# arduino_Uno_Rev3e.net
KiCad netlist of a schematic drawn in EAGLE
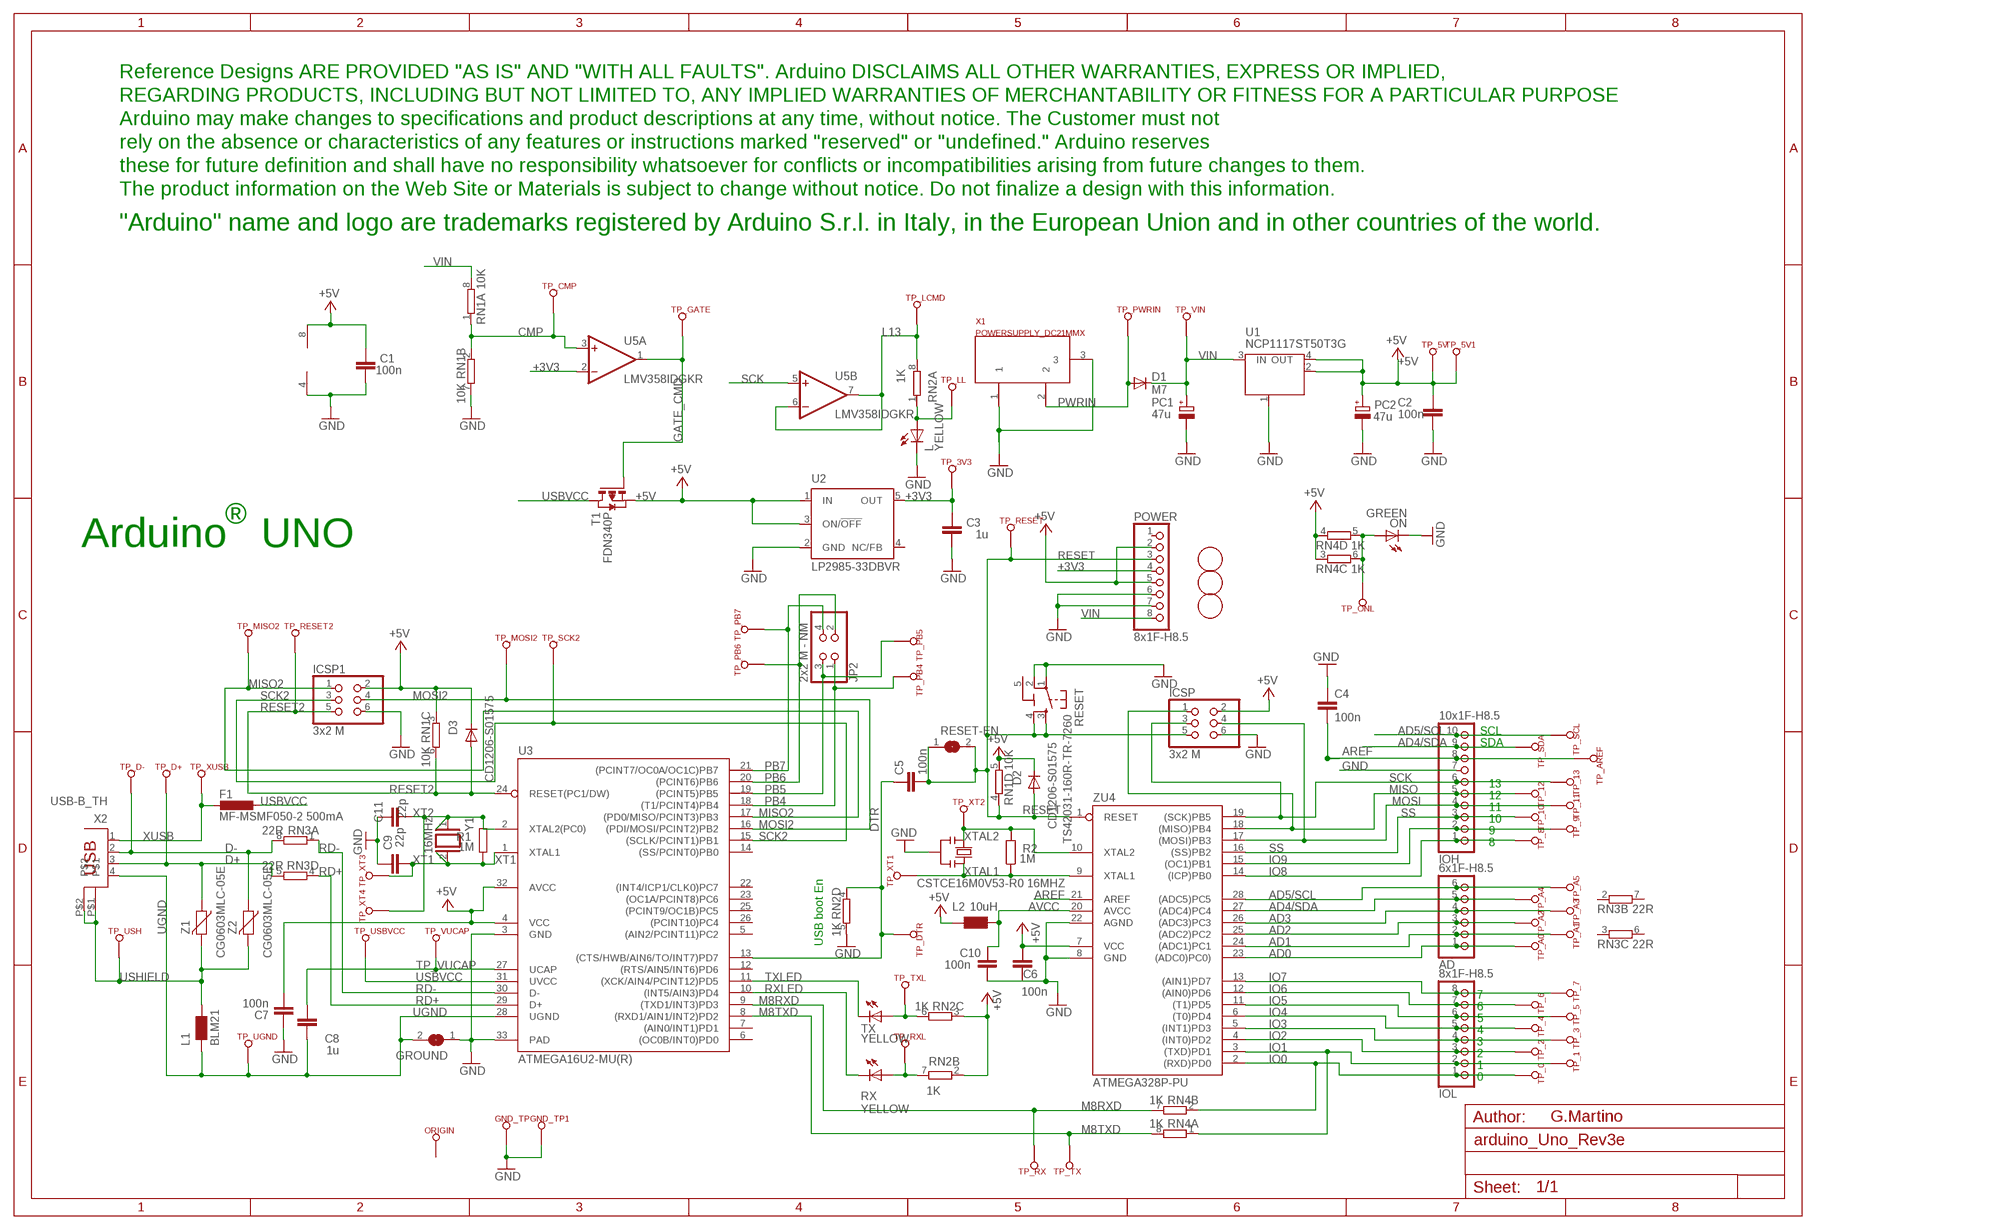
[diagram p0: schematic, sheet 1]

(export (version "E")
  (design (tool "Eeschema 10.0.6"))
  (components
    (comp (ref "AD")
      (value "6x1F-H8.5")
      (footprint "eagle-import:1X06")
      (libsource (lib "eagle-import") (part "PINHD-1X6"))
    )
    (comp (ref "C1")
      (value "100n")
      (footprint "eagle-import:C0603-ROUND")
      (libsource (lib "eagle-import") (part "C-EU0603-RND"))
    )
    (comp (ref "C2")
      (value "100n")
      (footprint "eagle-import:C0603-ROUND")
      (libsource (lib "eagle-import") (part "C-EU0603-RND"))
    )
    (comp (ref "C3")
      (value "1u")
      (footprint "eagle-import:C0603-ROUND")
      (libsource (lib "eagle-import") (part "C-EU0603-RND"))
    )
    (comp (ref "C4")
      (value "100n")
      (footprint "eagle-import:C0603-ROUND")
      (libsource (lib "eagle-import") (part "C-EU0603-RND"))
    )
    (comp (ref "C5")
      (value "100n")
      (footprint "eagle-import:C0603-ROUND")
      (libsource (lib "eagle-import") (part "C-EU0603-RND"))
    )
    (comp (ref "C6")
      (value "100n")
      (footprint "eagle-import:C0603-ROUND")
      (libsource (lib "eagle-import") (part "C-EU0603-RND"))
    )
    (comp (ref "C7")
      (value "100n")
      (footprint "eagle-import:C0603-ROUND")
      (libsource (lib "eagle-import") (part "C-EU0603-RND"))
    )
    (comp (ref "C8")
      (value "1u")
      (footprint "eagle-import:C0603-ROUND")
      (libsource (lib "eagle-import") (part "C-EU0603-RND"))
    )
    (comp (ref "C9")
      (value "22p")
      (footprint "eagle-import:C0603-ROUND")
      (libsource (lib "eagle-import") (part "C-EU0603-RND"))
    )
    (comp (ref "C10")
      (value "100n")
      (footprint "eagle-import:C0603-ROUND")
      (libsource (lib "eagle-import") (part "C-EU0603-RND"))
    )
    (comp (ref "C11")
      (value "22p")
      (footprint "eagle-import:C0603-ROUND")
      (libsource (lib "eagle-import") (part "C-EU0603-RND"))
    )
    (comp (ref "D1")
      (value "M7")
      (footprint "eagle-import:SMB")
      (libsource (lib "eagle-import") (part "DIODE-SMB"))
    )
    (comp (ref "D2")
      (value "CD1206-S01575")
      (footprint "eagle-import:MINIMELF")
      (libsource (lib "eagle-import") (part "DIODE-MINIMELF"))
    )
    (comp (ref "D3")
      (value "CD1206-S01575")
      (footprint "eagle-import:MINIMELF")
      (libsource (lib "eagle-import") (part "DIODE-MINIMELF"))
    )
    (comp (ref "F1")
      (value "MF-MSMF050-2 500mA")
      (footprint "eagle-import:L1812")
      (libsource (lib "eagle-import") (part "L-EUL1812"))
    )
    (comp (ref "FD1")
      (value "FIDUCIALMOUNT")
      (footprint "eagle-import:FIDUCIA-MOUNT")
      (libsource (lib "eagle-import") (part "FIDUCIALMOUNT"))
    )
    (comp (ref "FD2")
      (value "FIDUCIALMOUNT")
      (footprint "eagle-import:FIDUCIA-MOUNT")
      (libsource (lib "eagle-import") (part "FIDUCIALMOUNT"))
    )
    (comp (ref "FD3")
      (value "FIDUCIALMOUNT")
      (footprint "eagle-import:FIDUCIA-MOUNT")
      (libsource (lib "eagle-import") (part "FIDUCIALMOUNT"))
    )
    (comp (ref "GND_TP")
      (value "TP_SP")
      (footprint "eagle-import:TP-SP")
      (libsource (lib "eagle-import") (part "TP_SP"))
    )
    (comp (ref "GND_TP1")
      (value "TP_SP")
      (footprint "eagle-import:TP-SP")
      (libsource (lib "eagle-import") (part "TP_SP"))
    )
    (comp (ref "GROUND")
      (value "SJ")
      (footprint "eagle-import:SJ")
      (libsource (lib "eagle-import") (part "SJ"))
    )
    (comp (ref "ICSP")
      (value "3x2 M")
      (footprint "eagle-import:2X03")
      (libsource (lib "eagle-import") (part "PINHD-2X3"))
    )
    (comp (ref "ICSP1")
      (value "3x2 M")
      (footprint "eagle-import:2X03")
      (libsource (lib "eagle-import") (part "PINHD-2X3"))
    )
    (comp (ref "IOH")
      (value "10x1F-H8.5")
      (footprint "eagle-import:1X10")
      (libsource (lib "eagle-import") (part "PINHD-1X10_ARD"))
    )
    (comp (ref "IOL")
      (value "8x1F-H8.5")
      (footprint "eagle-import:1X08")
      (libsource (lib "eagle-import") (part "PINHD-1X8"))
    )
    (comp (ref "JP2")
      (value "2x2 M - NM")
      (footprint "eagle-import:2X02")
      (libsource (lib "eagle-import") (part "PINHD-2X2"))
    )
    (comp (ref "L")
      (value "YELLOW")
      (footprint "eagle-import:CHIP-LED0805")
      (libsource (lib "eagle-import") (part "LEDCHIP-LED0805"))
    )
    (comp (ref "L1")
      (value "BLM21")
      (footprint "eagle-import:0805")
      (libsource (lib "eagle-import") (part "WE-CBF_0805"))
    )
    (comp (ref "L2")
      (value "10uH")
      (footprint "eagle-import:0805")
      (fields (field (name "PART_NUMBER") "CV201210-100K"))
      (libsource (lib "eagle-import") (part "0715_CV201210-100K"))
    )
    (comp (ref "ON")
      (value "GREEN")
      (footprint "eagle-import:CHIP-LED0805")
      (libsource (lib "eagle-import") (part "LEDCHIP-LED0805"))
    )
    (comp (ref "ORIGIN")
      (value "TP_SP")
      (footprint "eagle-import:TP-SP")
      (libsource (lib "eagle-import") (part "TP_SP"))
    )
    (comp (ref "PC1")
      (value "47u")
      (footprint "eagle-import:PANASONIC_D")
      (libsource (lib "eagle-import") (part "CPOL-EUD"))
    )
    (comp (ref "PC2")
      (value "47u")
      (footprint "eagle-import:PANASONIC_D")
      (libsource (lib "eagle-import") (part "CPOL-EUD"))
    )
    (comp (ref "POWER")
      (value "8x1F-H8.5")
      (footprint "eagle-import:1X08")
      (libsource (lib "eagle-import") (part "PINHD-1X8"))
    )
    (comp (ref "R1")
      (value "1M")
      (footprint "eagle-import:R0603-ROUND")
      (libsource (lib "eagle-import") (part "R-EU_R0603"))
    )
    (comp (ref "R2")
      (value "1M")
      (footprint "eagle-import:R0603-ROUND")
      (libsource (lib "eagle-import") (part "R-EU_R0603"))
    )
    (comp (ref "RESET")
      (value "TS42031-160R-TR-7260")
      (footprint "eagle-import:TS42")
      (libsource (lib "eagle-import") (part "TS42"))
    )
    (comp (ref "RESET-EN")
      (value "SJ")
      (footprint "eagle-import:SJ")
      (libsource (lib "eagle-import") (part "SJ"))
    )
    (comp (ref "RN1")
      (value "10K")
      (footprint "eagle-import:CAY16")
      (libsource (lib "eagle-import") (part "4R-NCAY16"))
    )
    (comp (ref "RN2")
      (value "1K")
      (footprint "eagle-import:CAY16")
      (libsource (lib "eagle-import") (part "4R-NCAY16"))
    )
    (comp (ref "RN3")
      (value "22R")
      (footprint "eagle-import:CAY16")
      (libsource (lib "eagle-import") (part "4R-NCAY16"))
    )
    (comp (ref "RN4")
      (value "1K")
      (footprint "eagle-import:CAY16")
      (libsource (lib "eagle-import") (part "4R-NCAY16"))
    )
    (comp (ref "RX")
      (value "YELLOW")
      (footprint "eagle-import:CHIP-LED0805")
      (libsource (lib "eagle-import") (part "LEDCHIP-LED0805"))
    )
    (comp (ref "T1")
      (value "FDN340P")
      (footprint "eagle-import:SOT-23")
      (libsource (lib "eagle-import") (part "PMOSSOT23"))
    )
    (comp (ref "TP_0")
      (value "TP_SP")
      (footprint "eagle-import:TP-SP")
      (libsource (lib "eagle-import") (part "TP_SP"))
    )
    (comp (ref "TP_1")
      (value "TP_SP")
      (footprint "eagle-import:TP-SP")
      (libsource (lib "eagle-import") (part "TP_SP"))
    )
    (comp (ref "TP_2")
      (value "TP_SP")
      (footprint "eagle-import:TP-SP")
      (libsource (lib "eagle-import") (part "TP_SP"))
    )
    (comp (ref "TP_3")
      (value "TP_SP")
      (footprint "eagle-import:TP-SP")
      (libsource (lib "eagle-import") (part "TP_SP"))
    )
    (comp (ref "TP_3V3")
      (value "TP_SP")
      (footprint "eagle-import:TP-SP")
      (libsource (lib "eagle-import") (part "TP_SP"))
    )
    (comp (ref "TP_4")
      (value "TP_SP")
      (footprint "eagle-import:TP-SP")
      (libsource (lib "eagle-import") (part "TP_SP"))
    )
    (comp (ref "TP_5")
      (value "TP_SP")
      (footprint "eagle-import:TP-SP")
      (libsource (lib "eagle-import") (part "TP_SP"))
    )
    (comp (ref "TP_5V")
      (value "TP_SP")
      (footprint "eagle-import:TP-SP")
      (libsource (lib "eagle-import") (part "TP_SP"))
    )
    (comp (ref "TP_5V1")
      (value "TP_SP")
      (footprint "eagle-import:TP-SP")
      (libsource (lib "eagle-import") (part "TP_SP"))
    )
    (comp (ref "TP_6")
      (value "TP_SP")
      (footprint "eagle-import:TP-SP")
      (libsource (lib "eagle-import") (part "TP_SP"))
    )
    (comp (ref "TP_7")
      (value "TP_SP")
      (footprint "eagle-import:TP-SP")
      (libsource (lib "eagle-import") (part "TP_SP"))
    )
    (comp (ref "TP_8")
      (value "TP_SP")
      (footprint "eagle-import:TP-SP")
      (libsource (lib "eagle-import") (part "TP_SP"))
    )
    (comp (ref "TP_9")
      (value "TP_SP")
      (footprint "eagle-import:TP-SP")
      (libsource (lib "eagle-import") (part "TP_SP"))
    )
    (comp (ref "TP_10")
      (value "TP_SP")
      (footprint "eagle-import:TP-SP")
      (libsource (lib "eagle-import") (part "TP_SP"))
    )
    (comp (ref "TP_11")
      (value "TP_SP")
      (footprint "eagle-import:TP-SP")
      (libsource (lib "eagle-import") (part "TP_SP"))
    )
    (comp (ref "TP_12")
      (value "TP_SP")
      (footprint "eagle-import:TP-SP")
      (libsource (lib "eagle-import") (part "TP_SP"))
    )
    (comp (ref "TP_13")
      (value "TP_SP")
      (footprint "eagle-import:TP-SP")
      (libsource (lib "eagle-import") (part "TP_SP"))
    )
    (comp (ref "TP_A0")
      (value "TP_SP")
      (footprint "eagle-import:TP-SP")
      (libsource (lib "eagle-import") (part "TP_SP"))
    )
    (comp (ref "TP_A1")
      (value "TP_SP")
      (footprint "eagle-import:TP-SP")
      (libsource (lib "eagle-import") (part "TP_SP"))
    )
    (comp (ref "TP_A2")
      (value "TP_SP")
      (footprint "eagle-import:TP-SP")
      (libsource (lib "eagle-import") (part "TP_SP"))
    )
    (comp (ref "TP_A3")
      (value "TP_SP")
      (footprint "eagle-import:TP-SP")
      (libsource (lib "eagle-import") (part "TP_SP"))
    )
    (comp (ref "TP_A4")
      (value "TP_SP")
      (footprint "eagle-import:TP-SP")
      (libsource (lib "eagle-import") (part "TP_SP"))
    )
    (comp (ref "TP_A5")
      (value "TP_SP")
      (footprint "eagle-import:TP-SP")
      (libsource (lib "eagle-import") (part "TP_SP"))
    )
    (comp (ref "TP_AREF")
      (value "TP_SP")
      (footprint "eagle-import:TP-SP")
      (libsource (lib "eagle-import") (part "TP_SP"))
    )
    (comp (ref "TP_CMP")
      (value "TP_SP")
      (footprint "eagle-import:TP-SP")
      (libsource (lib "eagle-import") (part "TP_SP"))
    )
    (comp (ref "TP_D+")
      (value "TP_SP")
      (footprint "eagle-import:TP-SP")
      (libsource (lib "eagle-import") (part "TP_SP"))
    )
    (comp (ref "TP_D-")
      (value "TP_SP")
      (footprint "eagle-import:TP-SP")
      (libsource (lib "eagle-import") (part "TP_SP"))
    )
    (comp (ref "TP_DTR")
      (value "TP_SP")
      (footprint "eagle-import:TP-SP")
      (libsource (lib "eagle-import") (part "TP_SP"))
    )
    (comp (ref "TP_GATE")
      (value "TP_SP")
      (footprint "eagle-import:TP-SP")
      (libsource (lib "eagle-import") (part "TP_SP"))
    )
    (comp (ref "TP_LCMD")
      (value "TP_SP")
      (footprint "eagle-import:TP-SP")
      (libsource (lib "eagle-import") (part "TP_SP"))
    )
    (comp (ref "TP_LL")
      (value "TP_SP")
      (footprint "eagle-import:TP-SP")
      (libsource (lib "eagle-import") (part "TP_SP"))
    )
    (comp (ref "TP_MISO2")
      (value "TP_SP")
      (footprint "eagle-import:TP-SP")
      (libsource (lib "eagle-import") (part "TP_SP"))
    )
    (comp (ref "TP_MOSI2")
      (value "TP_SP")
      (footprint "eagle-import:TP-SP")
      (libsource (lib "eagle-import") (part "TP_SP"))
    )
    (comp (ref "TP_ONL")
      (value "TP_SP")
      (footprint "eagle-import:TP-SP")
      (libsource (lib "eagle-import") (part "TP_SP"))
    )
    (comp (ref "TP_PB4")
      (value "TP_SP")
      (footprint "eagle-import:TP-SP")
      (libsource (lib "eagle-import") (part "TP_SP"))
    )
    (comp (ref "TP_PB5")
      (value "TP_SP")
      (footprint "eagle-import:TP-SP")
      (libsource (lib "eagle-import") (part "TP_SP"))
    )
    (comp (ref "TP_PB6")
      (value "TP_SP")
      (footprint "eagle-import:TP-SP")
      (libsource (lib "eagle-import") (part "TP_SP"))
    )
    (comp (ref "TP_PB7")
      (value "TP_SP")
      (footprint "eagle-import:TP-SP")
      (libsource (lib "eagle-import") (part "TP_SP"))
    )
    (comp (ref "TP_PWRIN")
      (value "TP_SP")
      (footprint "eagle-import:TP-SP")
      (libsource (lib "eagle-import") (part "TP_SP"))
    )
    (comp (ref "TP_RESET")
      (value "TP_SP")
      (footprint "eagle-import:TP-SP")
      (libsource (lib "eagle-import") (part "TP_SP"))
    )
    (comp (ref "TP_RESET2")
      (value "TP_SP")
      (footprint "eagle-import:TP-SP")
      (libsource (lib "eagle-import") (part "TP_SP"))
    )
    (comp (ref "TP_RX")
      (value "TP_SP")
      (footprint "eagle-import:TP-SP")
      (libsource (lib "eagle-import") (part "TP_SP"))
    )
    (comp (ref "TP_RXL")
      (value "TP_SP")
      (footprint "eagle-import:TP-SP")
      (libsource (lib "eagle-import") (part "TP_SP"))
    )
    (comp (ref "TP_SCK2")
      (value "TP_SP")
      (footprint "eagle-import:TP-SP")
      (libsource (lib "eagle-import") (part "TP_SP"))
    )
    (comp (ref "TP_SCL")
      (value "TP_SP")
      (footprint "eagle-import:TP-SP")
      (libsource (lib "eagle-import") (part "TP_SP"))
    )
    (comp (ref "TP_SDA")
      (value "TP_SP")
      (footprint "eagle-import:TP-SP")
      (libsource (lib "eagle-import") (part "TP_SP"))
    )
    (comp (ref "TP_TX")
      (value "TP_SP")
      (footprint "eagle-import:TP-SP")
      (libsource (lib "eagle-import") (part "TP_SP"))
    )
    (comp (ref "TP_TXL")
      (value "TP_SP")
      (footprint "eagle-import:TP-SP")
      (libsource (lib "eagle-import") (part "TP_SP"))
    )
    (comp (ref "TP_UGND")
      (value "TP_SP")
      (footprint "eagle-import:TP-SP")
      (libsource (lib "eagle-import") (part "TP_SP"))
    )
    (comp (ref "TP_USBVCC")
      (value "TP_SP")
      (footprint "eagle-import:TP-SP")
      (libsource (lib "eagle-import") (part "TP_SP"))
    )
    (comp (ref "TP_USH")
      (value "TP_SP")
      (footprint "eagle-import:TP-SP")
      (libsource (lib "eagle-import") (part "TP_SP"))
    )
    (comp (ref "TP_VIN")
      (value "TP_SP")
      (footprint "eagle-import:TP-SP")
      (libsource (lib "eagle-import") (part "TP_SP"))
    )
    (comp (ref "TP_VUCAP")
      (value "TP_SP")
      (footprint "eagle-import:TP-SP")
      (libsource (lib "eagle-import") (part "TP_SP"))
    )
    (comp (ref "TP_XT1")
      (value "TP_SP")
      (footprint "eagle-import:TP-SP")
      (libsource (lib "eagle-import") (part "TP_SP"))
    )
    (comp (ref "TP_XT2")
      (value "TP_SP")
      (footprint "eagle-import:TP-SP")
      (libsource (lib "eagle-import") (part "TP_SP"))
    )
    (comp (ref "TP_XT3")
      (value "TP_SP")
      (footprint "eagle-import:TP-SP")
      (libsource (lib "eagle-import") (part "TP_SP"))
    )
    (comp (ref "TP_XT4")
      (value "TP_SP")
      (footprint "eagle-import:TP-SP")
      (libsource (lib "eagle-import") (part "TP_SP"))
    )
    (comp (ref "TP_XUSB")
      (value "TP_SP")
      (footprint "eagle-import:TP-SP")
      (libsource (lib "eagle-import") (part "TP_SP"))
    )
    (comp (ref "TX")
      (value "YELLOW")
      (footprint "eagle-import:CHIP-LED0805")
      (libsource (lib "eagle-import") (part "LEDCHIP-LED0805"))
    )
    (comp (ref "U$1")
      (value "DISCLAIMER")
      (footprint "eagle-import:DISCLAIMER")
      (libsource (lib "eagle-import") (part "DISCLAIMER"))
    )
    (comp (ref "U1")
      (value "NCP1117ST50T3G")
      (footprint "eagle-import:SOT223")
      (libsource (lib "eagle-import") (part "MC33269ST-3.3T3"))
    )
    (comp (ref "U2")
      (value "LP2985-33DBVR")
      (footprint "eagle-import:SOT23-DBV")
      (libsource (lib "eagle-import") (part "LP2985-XXDBVR33"))
    )
    (comp (ref "U3")
      (value "ATMEGA16U2-MU(R)")
      (footprint "eagle-import:MLF32")
      (libsource (lib "eagle-import") (part "ATMEGA16U2-MU"))
    )
    (comp (ref "U5")
      (value "LMV358IDGKR")
      (footprint "eagle-import:MSOP08")
      (libsource (lib "eagle-import") (part "LMV358?MMX"))
    )
    (comp (ref "X1")
      (value "POWERSUPPLY_DC21MMX")
      (footprint "eagle-import:POWERSUPPLY_DC-21MM")
      (libsource (lib "eagle-import") (part "POWERSUPPLY_DC21MMX"))
    )
    (comp (ref "X2")
      (value "USB-B_TH")
      (footprint "eagle-import:PN61729")
      (libsource (lib "eagle-import") (part "PN61729"))
    )
    (comp (ref "Y1")
      (value "16MHz")
      (footprint "eagle-import:QS")
      (libsource (lib "eagle-import") (part "XTAL/S"))
    )
    (comp (ref "Y2")
      (value "CSTCE16M0V53-R0 16MHZ")
      (footprint "eagle-import:RESONATOR")
      (libsource (lib "eagle-import") (part "RESONATORMU"))
    )
    (comp (ref "Z1")
      (value "CG0603MLC-05E")
      (footprint "eagle-import:CT_CN0603")
      (libsource (lib "eagle-import") (part "VARISTORCN0603"))
    )
    (comp (ref "Z2")
      (value "CG0603MLC-05E")
      (footprint "eagle-import:CT_CN0603")
      (libsource (lib "eagle-import") (part "VARISTORCN0603"))
    )
    (comp (ref "ZU4")
      (value "ATMEGA328P-PU")
      (footprint "eagle-import:DIL28-3")
      (libsource (lib "eagle-import") (part "ATMEGA328P-PU"))
    )
  )
  (nets
    (net (code "1") (name "+5V") (class "Default")
      (node (ref "C1") (pin "2") (pinfunction "2_2") (pintype "passive"))
      (node (ref "C2") (pin "2") (pinfunction "2_2") (pintype "passive"))
      (node (ref "C6") (pin "2") (pinfunction "2_2") (pintype "passive"))
      (node (ref "C7") (pin "1") (pinfunction "1_1") (pintype "passive"))
      (node (ref "D2") (pin "C") (pinfunction "C_C") (pintype "passive"))
      (node (ref "D3") (pin "C") (pinfunction "C_C") (pintype "passive"))
      (node (ref "ICSP") (pin "2") (pinfunction "2_2") (pintype "passive"))
      (node (ref "ICSP1") (pin "2") (pinfunction "2_2") (pintype "passive"))
      (node (ref "L2") (pin "1") (pinfunction "1_1") (pintype "passive"))
      (node (ref "PC2") (pin "+") (pinfunction "+_+") (pintype "passive"))
      (node (ref "POWER") (pin "2") (pinfunction "2_2") (pintype "passive"))
      (node (ref "POWER") (pin "5") (pinfunction "5_5") (pintype "passive"))
      (node (ref "RN1") (pin "3") (pinfunction "1_3") (pintype "passive"))
      (node (ref "RN1") (pin "5") (pinfunction "2_5") (pintype "passive"))
      (node (ref "RN2") (pin "2") (pinfunction "1_2") (pintype "passive"))
      (node (ref "RN2") (pin "3") (pinfunction "1_3") (pintype "passive"))
      (node (ref "RN4") (pin "3") (pinfunction "1_3") (pintype "passive"))
      (node (ref "RN4") (pin "4") (pinfunction "1_4") (pintype "passive"))
      (node (ref "T1") (pin "2") (pinfunction "S_2") (pintype "passive"))
      (node (ref "TP_5V") (pin "X") (pinfunction "TESTP_X") (pintype "passive"))
      (node (ref "TP_5V1") (pin "X") (pinfunction "TESTP_X") (pintype "passive"))
      (node (ref "U1") (pin "2") (pinfunction "OUT_2") (pintype "passive"))
      (node (ref "U1") (pin "4") (pinfunction "OUT_4") (pintype "passive"))
      (node (ref "U2") (pin "1") (pinfunction "IN_1") (pintype "input"))
      (node (ref "U2") (pin "3") (pinfunction "ON/~{OFF}_3") (pintype "input"))
      (node (ref "U3") (pin "32") (pinfunction "AVCC_32") (pintype "power_in"))
      (node (ref "U3") (pin "4") (pinfunction "VCC_4") (pintype "power_in"))
      (node (ref "U5") (pin "8") (pinfunction "V+_8") (pintype "power_in"))
      (node (ref "ZU4") (pin "7") (pinfunction "VCC_7") (pintype "power_in"))
    )
    (net (code "2") (name "/+3V3") (class "Default")
      (node (ref "C3") (pin "2") (pinfunction "2_2") (pintype "passive"))
      (node (ref "POWER") (pin "4") (pinfunction "4_4") (pintype "passive"))
      (node (ref "TP_3V3") (pin "X") (pinfunction "TESTP_X") (pintype "passive"))
      (node (ref "U2") (pin "5") (pinfunction "OUT_5") (pintype "passive"))
      (node (ref "U5") (pin "2") (pinfunction "-IN_2") (pintype "input"))
    )
    (net (code "3") (name "/5-GND") (class "Default")
      (node (ref "RESET") (pin "5") (pinfunction "5-GND_5") (pintype "power_in"))
    )
    (net (code "4") (name "/AD0") (class "Default")
      (node (ref "AD") (pin "1") (pinfunction "1_1") (pintype "passive"))
      (node (ref "TP_A0") (pin "X") (pinfunction "TESTP_X") (pintype "passive"))
      (node (ref "ZU4") (pin "23") (pinfunction "(ADC0)PC0)_23") (pintype "bidirectional"))
    )
    (net (code "5") (name "/AD1") (class "Default")
      (node (ref "AD") (pin "2") (pinfunction "2_2") (pintype "passive"))
      (node (ref "TP_A1") (pin "X") (pinfunction "TESTP_X") (pintype "passive"))
      (node (ref "ZU4") (pin "24") (pinfunction "(ADC1)PC1_24") (pintype "bidirectional"))
    )
    (net (code "6") (name "/AD2") (class "Default")
      (node (ref "AD") (pin "3") (pinfunction "3_3") (pintype "passive"))
      (node (ref "TP_A2") (pin "X") (pinfunction "TESTP_X") (pintype "passive"))
      (node (ref "ZU4") (pin "25") (pinfunction "(ADC2)PC2_25") (pintype "bidirectional"))
    )
    (net (code "7") (name "/AD3") (class "Default")
      (node (ref "AD") (pin "4") (pinfunction "4_4") (pintype "passive"))
      (node (ref "TP_A3") (pin "X") (pinfunction "TESTP_X") (pintype "passive"))
      (node (ref "ZU4") (pin "26") (pinfunction "(ADC3)PC3_26") (pintype "bidirectional"))
    )
    (net (code "8") (name "/AD4{slash}SDA") (class "Default")
      (node (ref "AD") (pin "5") (pinfunction "5_5") (pintype "passive"))
      (node (ref "IOH") (pin "9") (pinfunction "9_9") (pintype "passive"))
      (node (ref "TP_A4") (pin "X") (pinfunction "TESTP_X") (pintype "passive"))
      (node (ref "TP_SDA") (pin "X") (pinfunction "TESTP_X") (pintype "passive"))
      (node (ref "ZU4") (pin "27") (pinfunction "(ADC4)PC4_27") (pintype "bidirectional"))
    )
    (net (code "9") (name "/AD5{slash}SCL") (class "Default")
      (node (ref "AD") (pin "6") (pinfunction "6_6") (pintype "passive"))
      (node (ref "IOH") (pin "10") (pinfunction "10_10") (pintype "passive"))
      (node (ref "TP_A5") (pin "X") (pinfunction "TESTP_X") (pintype "passive"))
      (node (ref "TP_SCL") (pin "X") (pinfunction "TESTP_X") (pintype "passive"))
      (node (ref "ZU4") (pin "28") (pinfunction "(ADC5)PC5_28") (pintype "bidirectional"))
    )
    (net (code "10") (name "/AREF") (class "Default")
      (node (ref "C4") (pin "2") (pinfunction "2_2") (pintype "passive"))
      (node (ref "IOH") (pin "8") (pinfunction "8_8") (pintype "passive"))
      (node (ref "TP_AREF") (pin "X") (pinfunction "TESTP_X") (pintype "passive"))
      (node (ref "ZU4") (pin "21") (pinfunction "AREF_21") (pintype "passive"))
    )
    (net (code "11") (name "/AVCC") (class "Default")
      (node (ref "C10") (pin "2") (pinfunction "2_2") (pintype "passive"))
      (node (ref "L2") (pin "2") (pinfunction "2_2") (pintype "passive"))
      (node (ref "ZU4") (pin "20") (pinfunction "AVCC_20") (pintype "power_in"))
    )
    (net (code "12") (name "/CMP") (class "Default")
      (node (ref "RN1") (pin "1") (pinfunction "1_1") (pintype "passive"))
      (node (ref "RN1") (pin "2") (pinfunction "1_2") (pintype "passive"))
      (node (ref "TP_CMP") (pin "X") (pinfunction "TESTP_X") (pintype "passive"))
      (node (ref "U5") (pin "3") (pinfunction "+IN_3") (pintype "input"))
    )
    (net (code "13") (name "/D+") (class "Default")
      (node (ref "RN3") (pin "5") (pinfunction "2_5") (pintype "passive"))
      (node (ref "TP_D+") (pin "X") (pinfunction "TESTP_X") (pintype "passive"))
      (node (ref "X2") (pin "3") (pinfunction "3_3") (pintype "bidirectional"))
      (node (ref "Z1") (pin "1") (pinfunction "1_1") (pintype "passive"))
    )
    (net (code "14") (name "/D-") (class "Default")
      (node (ref "RN3") (pin "8") (pinfunction "2_8") (pintype "passive"))
      (node (ref "TP_D-") (pin "X") (pinfunction "TESTP_X") (pintype "passive"))
      (node (ref "X2") (pin "2") (pinfunction "2_2") (pintype "bidirectional"))
      (node (ref "Z2") (pin "1") (pinfunction "1_1") (pintype "passive"))
    )
    (net (code "15") (name "/DTR") (class "Default")
      (node (ref "C5") (pin "1") (pinfunction "1_1") (pintype "passive"))
      (node (ref "RN2") (pin "4") (pinfunction "1_4") (pintype "passive"))
      (node (ref "TP_DTR") (pin "X") (pinfunction "TESTP_X") (pintype "passive"))
      (node (ref "U3") (pin "13") (pinfunction "(CTS/HWB/AIN6/TO/INT7)PD7_13") (pintype "bidirectional"))
    )
    (net (code "16") (name "/GATE_CMD") (class "Default")
      (node (ref "T1") (pin "3") (pinfunction "G_3") (pintype "passive"))
      (node (ref "TP_GATE") (pin "X") (pinfunction "TESTP_X") (pintype "passive"))
      (node (ref "U5") (pin "1") (pinfunction "OUT_1") (pintype "output"))
    )
    (net (code "17") (name "/IO0") (class "Default")
      (node (ref "IOL") (pin "1") (pinfunction "1_1") (pintype "passive"))
      (node (ref "RN4") (pin "2") (pinfunction "1_2") (pintype "passive"))
      (node (ref "TP_0") (pin "X") (pinfunction "TESTP_X") (pintype "passive"))
      (node (ref "ZU4") (pin "2") (pinfunction "(RXD)PD0_2") (pintype "bidirectional"))
    )
    (net (code "18") (name "/IO1") (class "Default")
      (node (ref "IOL") (pin "2") (pinfunction "2_2") (pintype "passive"))
      (node (ref "RN4") (pin "1") (pinfunction "1_1") (pintype "passive"))
      (node (ref "TP_1") (pin "X") (pinfunction "TESTP_X") (pintype "passive"))
      (node (ref "ZU4") (pin "3") (pinfunction "(TXD)PD1_3") (pintype "bidirectional"))
    )
    (net (code "19") (name "/IO2") (class "Default")
      (node (ref "IOL") (pin "3") (pinfunction "3_3") (pintype "passive"))
      (node (ref "TP_2") (pin "X") (pinfunction "TESTP_X") (pintype "passive"))
      (node (ref "ZU4") (pin "4") (pinfunction "(INT0)PD2_4") (pintype "bidirectional"))
    )
    (net (code "20") (name "/IO3") (class "Default")
      (node (ref "IOL") (pin "4") (pinfunction "4_4") (pintype "passive"))
      (node (ref "TP_3") (pin "X") (pinfunction "TESTP_X") (pintype "passive"))
      (node (ref "ZU4") (pin "5") (pinfunction "(INT1)PD3_5") (pintype "bidirectional"))
    )
    (net (code "21") (name "/IO4") (class "Default")
      (node (ref "IOL") (pin "5") (pinfunction "5_5") (pintype "passive"))
      (node (ref "TP_4") (pin "X") (pinfunction "TESTP_X") (pintype "passive"))
      (node (ref "ZU4") (pin "6") (pinfunction "(T0)PD4_6") (pintype "bidirectional"))
    )
    (net (code "22") (name "/IO5") (class "Default")
      (node (ref "IOL") (pin "6") (pinfunction "6_6") (pintype "passive"))
      (node (ref "TP_5") (pin "X") (pinfunction "TESTP_X") (pintype "passive"))
      (node (ref "ZU4") (pin "11") (pinfunction "(T1)PD5_11") (pintype "bidirectional"))
    )
    (net (code "23") (name "/IO6") (class "Default")
      (node (ref "IOL") (pin "7") (pinfunction "7_7") (pintype "passive"))
      (node (ref "TP_6") (pin "X") (pinfunction "TESTP_X") (pintype "passive"))
      (node (ref "ZU4") (pin "12") (pinfunction "(AIN0)PD6_12") (pintype "bidirectional"))
    )
    (net (code "24") (name "/IO7") (class "Default")
      (node (ref "IOL") (pin "8") (pinfunction "8_8") (pintype "passive"))
      (node (ref "TP_7") (pin "X") (pinfunction "TESTP_X") (pintype "passive"))
      (node (ref "ZU4") (pin "13") (pinfunction "(AIN1)PD7_13") (pintype "bidirectional"))
    )
    (net (code "25") (name "/IO8") (class "Default")
      (node (ref "IOH") (pin "1") (pinfunction "1_1") (pintype "passive"))
      (node (ref "TP_8") (pin "X") (pinfunction "TESTP_X") (pintype "passive"))
      (node (ref "ZU4") (pin "14") (pinfunction "(ICP)PB0_14") (pintype "bidirectional"))
    )
    (net (code "26") (name "/IO9") (class "Default")
      (node (ref "IOH") (pin "2") (pinfunction "2_2") (pintype "passive"))
      (node (ref "TP_9") (pin "X") (pinfunction "TESTP_X") (pintype "passive"))
      (node (ref "ZU4") (pin "15") (pinfunction "(OC1)PB1_15") (pintype "bidirectional"))
    )
    (net (code "27") (name "/L13") (class "Default")
      (node (ref "RN2") (pin "8") (pinfunction "2_8") (pintype "passive"))
      (node (ref "TP_LCMD") (pin "X") (pinfunction "TESTP_X") (pintype "passive"))
      (node (ref "U5") (pin "6") (pinfunction "-IN_6") (pintype "input"))
      (node (ref "U5") (pin "7") (pinfunction "OUT_7") (pintype "output"))
    )
    (net (code "28") (name "/M8RXD") (class "Default")
      (node (ref "RN4") (pin "7") (pinfunction "2_7") (pintype "passive"))
      (node (ref "TP_RX") (pin "X") (pinfunction "TESTP_X") (pintype "passive"))
      (node (ref "U3") (pin "9") (pinfunction "(TXD1/INT3)PD3_9") (pintype "bidirectional"))
    )
    (net (code "29") (name "/M8TXD") (class "Default")
      (node (ref "RN4") (pin "8") (pinfunction "2_8") (pintype "passive"))
      (node (ref "TP_TX") (pin "X") (pinfunction "TESTP_X") (pintype "passive"))
      (node (ref "U3") (pin "8") (pinfunction "(RXD1/AIN1/INT2)PD2_8") (pintype "bidirectional"))
    )
    (net (code "30") (name "/MISO") (class "Default")
      (node (ref "ICSP") (pin "1") (pinfunction "1_1") (pintype "passive"))
      (node (ref "IOH") (pin "5") (pinfunction "5_5") (pintype "passive"))
      (node (ref "TP_12") (pin "X") (pinfunction "TESTP_X") (pintype "passive"))
      (node (ref "ZU4") (pin "18") (pinfunction "(MISO)PB4_18") (pintype "bidirectional"))
    )
    (net (code "31") (name "/MISO2") (class "Default")
      (node (ref "ICSP1") (pin "1") (pinfunction "1_1") (pintype "passive"))
      (node (ref "TP_MISO2") (pin "X") (pinfunction "TESTP_X") (pintype "passive"))
      (node (ref "U3") (pin "17") (pinfunction "(PD0/MISO/PCINT3)PB3_17") (pintype "bidirectional"))
    )
    (net (code "32") (name "/MOSI") (class "Default")
      (node (ref "ICSP") (pin "4") (pinfunction "4_4") (pintype "passive"))
      (node (ref "IOH") (pin "4") (pinfunction "4_4") (pintype "passive"))
      (node (ref "TP_11") (pin "X") (pinfunction "TESTP_X") (pintype "passive"))
      (node (ref "ZU4") (pin "17") (pinfunction "(MOSI)PB3_17") (pintype "bidirectional"))
    )
    (net (code "33") (name "/MOSI2") (class "Default")
      (node (ref "ICSP1") (pin "4") (pinfunction "4_4") (pintype "passive"))
      (node (ref "TP_MOSI2") (pin "X") (pinfunction "TESTP_X") (pintype "passive"))
      (node (ref "U3") (pin "16") (pinfunction "(PDI/MOSI/PCINT2)PB2_16") (pintype "bidirectional"))
    )
    (net (code "34") (name "/PB4") (class "Default")
      (node (ref "JP2") (pin "1") (pinfunction "1_1") (pintype "passive"))
      (node (ref "TP_PB4") (pin "X") (pinfunction "TESTP_X") (pintype "passive"))
      (node (ref "U3") (pin "18") (pinfunction "(T1/PCINT4)PB4_18") (pintype "bidirectional"))
    )
    (net (code "35") (name "/PB5") (class "Default")
      (node (ref "JP2") (pin "3") (pinfunction "3_3") (pintype "passive"))
      (node (ref "TP_PB5") (pin "X") (pinfunction "TESTP_X") (pintype "passive"))
      (node (ref "U3") (pin "19") (pinfunction "(PCINT5)PB5_19") (pintype "bidirectional"))
    )
    (net (code "36") (name "/PB6") (class "Default")
      (node (ref "JP2") (pin "2") (pinfunction "2_2") (pintype "passive"))
      (node (ref "TP_PB6") (pin "X") (pinfunction "TESTP_X") (pintype "passive"))
      (node (ref "U3") (pin "20") (pinfunction "(PCINT6)PB6_20") (pintype "bidirectional"))
    )
    (net (code "37") (name "/PB7") (class "Default")
      (node (ref "JP2") (pin "4") (pinfunction "4_4") (pintype "passive"))
      (node (ref "TP_PB7") (pin "X") (pinfunction "TESTP_X") (pintype "passive"))
      (node (ref "U3") (pin "21") (pinfunction "(PCINT7/OC0A/OC1C)PB7_21") (pintype "bidirectional"))
    )
    (net (code "38") (name "/PWRIN") (class "Default")
      (node (ref "D1") (pin "A") (pinfunction "A_A") (pintype "passive"))
      (node (ref "TP_PWRIN") (pin "X") (pinfunction "TESTP_X") (pintype "passive"))
      (node (ref "X1") (pin "2") (pinfunction "2_2") (pintype "power_in"))
    )
    (net (code "39") (name "/RD+") (class "Default")
      (node (ref "RN3") (pin "4") (pinfunction "1_4") (pintype "passive"))
      (node (ref "U3") (pin "29") (pinfunction "D+_29") (pintype "bidirectional"))
    )
    (net (code "40") (name "/RD-") (class "Default")
      (node (ref "RN3") (pin "1") (pinfunction "1_1") (pintype "passive"))
      (node (ref "U3") (pin "30") (pinfunction "D-_30") (pintype "bidirectional"))
    )
    (net (code "41") (name "/RESET") (class "Default")
      (node (ref "C5") (pin "2") (pinfunction "2_2") (pintype "passive"))
      (node (ref "D2") (pin "A") (pinfunction "A_A") (pintype "passive"))
      (node (ref "ICSP") (pin "5") (pinfunction "5_5") (pintype "passive"))
      (node (ref "POWER") (pin "3") (pinfunction "3_3") (pintype "passive"))
      (node (ref "RESET") (pin "3") (pinfunction "3_3") (pintype "passive"))
      (node (ref "RESET") (pin "4") (pinfunction "4_4") (pintype "passive"))
      (node (ref "RESET-EN") (pin "1") (pinfunction "1_1") (pintype "passive"))
      (node (ref "RESET-EN") (pin "2") (pinfunction "2_2") (pintype "passive"))
      (node (ref "RN1") (pin "4") (pinfunction "1_4") (pintype "passive"))
      (node (ref "TP_RESET") (pin "X") (pinfunction "TESTP_X") (pintype "passive"))
      (node (ref "ZU4") (pin "1") (pinfunction "RESET_1") (pintype "input"))
    )
    (net (code "42") (name "/RESET2") (class "Default")
      (node (ref "D3") (pin "A") (pinfunction "A_A") (pintype "passive"))
      (node (ref "ICSP1") (pin "5") (pinfunction "5_5") (pintype "passive"))
      (node (ref "RN1") (pin "6") (pinfunction "2_6") (pintype "passive"))
      (node (ref "TP_RESET2") (pin "X") (pinfunction "TESTP_X") (pintype "passive"))
      (node (ref "U3") (pin "24") (pinfunction "RESET(PC1/DW)_24") (pintype "input"))
    )
    (net (code "43") (name "/RXLED") (class "Default")
      (node (ref "RX") (pin "C") (pinfunction "C_C") (pintype "passive"))
      (node (ref "U3") (pin "10") (pinfunction "(INT5/AIN3)PD4_10") (pintype "bidirectional"))
    )
    (net (code "44") (name "/SCK") (class "Default")
      (node (ref "ICSP") (pin "3") (pinfunction "3_3") (pintype "passive"))
      (node (ref "IOH") (pin "6") (pinfunction "6_6") (pintype "passive"))
      (node (ref "TP_13") (pin "X") (pinfunction "TESTP_X") (pintype "passive"))
      (node (ref "U5") (pin "5") (pinfunction "+IN_5") (pintype "input"))
      (node (ref "ZU4") (pin "19") (pinfunction "(SCK)PB5_19") (pintype "bidirectional"))
    )
    (net (code "45") (name "/SCK2") (class "Default")
      (node (ref "ICSP1") (pin "3") (pinfunction "3_3") (pintype "passive"))
      (node (ref "TP_SCK2") (pin "X") (pinfunction "TESTP_X") (pintype "passive"))
      (node (ref "U3") (pin "15") (pinfunction "(SCLK/PCINT1)PB1_15") (pintype "bidirectional"))
    )
    (net (code "46") (name "/SS") (class "Default")
      (node (ref "IOH") (pin "3") (pinfunction "3_3") (pintype "passive"))
      (node (ref "TP_10") (pin "X") (pinfunction "TESTP_X") (pintype "passive"))
      (node (ref "ZU4") (pin "16") (pinfunction "(SS)PB2_16") (pintype "bidirectional"))
    )
    (net (code "47") (name "/TP_VUCAP") (class "Default")
      (node (ref "C8") (pin "1") (pinfunction "1_1") (pintype "passive"))
      (node (ref "TP_VUCAP") (pin "X") (pinfunction "TESTP_X") (pintype "passive"))
      (node (ref "U3") (pin "27") (pinfunction "UCAP_27") (pintype "passive"))
    )
    (net (code "48") (name "/TXLED") (class "Default")
      (node (ref "TX") (pin "C") (pinfunction "C_C") (pintype "passive"))
      (node (ref "U3") (pin "11") (pinfunction "(XCK/AIN4/PCINT12)PD5_11") (pintype "bidirectional"))
    )
    (net (code "49") (name "/UGND") (class "Default")
      (node (ref "C8") (pin "2") (pinfunction "2_2") (pintype "passive"))
      (node (ref "GROUND") (pin "2") (pinfunction "2_2") (pintype "passive"))
      (node (ref "L1") (pin "1") (pinfunction "1_1") (pintype "passive"))
      (node (ref "TP_UGND") (pin "X") (pinfunction "TESTP_X") (pintype "passive"))
      (node (ref "U3") (pin "28") (pinfunction "UGND_28") (pintype "power_in"))
      (node (ref "X2") (pin "4") (pinfunction "4_4") (pintype "bidirectional"))
    )
    (net (code "50") (name "/USBVCC") (class "Default")
      (node (ref "F1") (pin "1") (pinfunction "1_1") (pintype "passive"))
      (node (ref "T1") (pin "1") (pinfunction "D_1") (pintype "passive"))
      (node (ref "TP_USBVCC") (pin "X") (pinfunction "TESTP_X") (pintype "passive"))
      (node (ref "U3") (pin "31") (pinfunction "UVCC_31") (pintype "power_in"))
    )
    (net (code "51") (name "/USHIELD") (class "Default")
      (node (ref "L1") (pin "2") (pinfunction "2_2") (pintype "passive"))
      (node (ref "TP_USH") (pin "X") (pinfunction "TESTP_X") (pintype "passive"))
      (node (ref "X2") (pin "P$1") (pinfunction "P$1_P$1") (pintype "bidirectional"))
      (node (ref "X2") (pin "P$2") (pinfunction "P$2_P$2") (pintype "bidirectional"))
      (node (ref "Z1") (pin "2") (pinfunction "2_2") (pintype "passive"))
      (node (ref "Z2") (pin "2") (pinfunction "2_2") (pintype "passive"))
    )
    (net (code "52") (name "/VIN") (class "Default")
      (node (ref "D1") (pin "C") (pinfunction "C_C") (pintype "passive"))
      (node (ref "PC1") (pin "+") (pinfunction "+_+") (pintype "passive"))
      (node (ref "POWER") (pin "8") (pinfunction "8_8") (pintype "passive"))
      (node (ref "RN1") (pin "8") (pinfunction "2_8") (pintype "passive"))
      (node (ref "TP_VIN") (pin "X") (pinfunction "TESTP_X") (pintype "passive"))
      (node (ref "U1") (pin "3") (pinfunction "IN_3") (pintype "input"))
    )
    (net (code "53") (name "/XT1") (class "Default")
      (node (ref "C9") (pin "1") (pinfunction "1_1") (pintype "passive"))
      (node (ref "R1") (pin "1") (pinfunction "1_1") (pintype "passive"))
      (node (ref "TP_XT3") (pin "X") (pinfunction "TESTP_X") (pintype "passive"))
      (node (ref "U3") (pin "1") (pinfunction "XTAL1_1") (pintype "bidirectional"))
      (node (ref "Y1") (pin "2") (pinfunction "2_2") (pintype "passive"))
    )
    (net (code "54") (name "/XT2") (class "Default")
      (node (ref "C11") (pin "1") (pinfunction "1_1") (pintype "passive"))
      (node (ref "R1") (pin "2") (pinfunction "2_2") (pintype "passive"))
      (node (ref "TP_XT4") (pin "X") (pinfunction "TESTP_X") (pintype "passive"))
      (node (ref "U3") (pin "2") (pinfunction "XTAL2(PC0)_2") (pintype "bidirectional"))
      (node (ref "Y1") (pin "1") (pinfunction "1_1") (pintype "passive"))
    )
    (net (code "55") (name "/XTAL1") (class "Default")
      (node (ref "R2") (pin "1") (pinfunction "1_1") (pintype "passive"))
      (node (ref "TP_XT1") (pin "X") (pinfunction "TESTP_X") (pintype "passive"))
      (node (ref "Y2") (pin "3") (pinfunction "3_3") (pintype "passive"))
      (node (ref "ZU4") (pin "9") (pinfunction "XTAL1_9") (pintype "bidirectional"))
    )
    (net (code "56") (name "/XTAL2") (class "Default")
      (node (ref "R2") (pin "2") (pinfunction "2_2") (pintype "passive"))
      (node (ref "TP_XT2") (pin "X") (pinfunction "TESTP_X") (pintype "passive"))
      (node (ref "Y2") (pin "1") (pinfunction "1_1") (pintype "passive"))
      (node (ref "ZU4") (pin "10") (pinfunction "XTAL2_10") (pintype "bidirectional"))
    )
    (net (code "57") (name "/XUSB") (class "Default")
      (node (ref "F1") (pin "2") (pinfunction "2_2") (pintype "passive"))
      (node (ref "TP_XUSB") (pin "X") (pinfunction "TESTP_X") (pintype "passive"))
      (node (ref "X2") (pin "1") (pinfunction "1_1") (pintype "bidirectional"))
    )
    (net (code "58") (name "GND") (class "Default")
      (node (ref "C1") (pin "1") (pinfunction "1_1") (pintype "passive"))
      (node (ref "C10") (pin "1") (pinfunction "1_1") (pintype "passive"))
      (node (ref "C11") (pin "2") (pinfunction "2_2") (pintype "passive"))
      (node (ref "C2") (pin "1") (pinfunction "1_1") (pintype "passive"))
      (node (ref "C3") (pin "1") (pinfunction "1_1") (pintype "passive"))
      (node (ref "C4") (pin "1") (pinfunction "1_1") (pintype "passive"))
      (node (ref "C6") (pin "1") (pinfunction "1_1") (pintype "passive"))
      (node (ref "C7") (pin "2") (pinfunction "2_2") (pintype "passive"))
      (node (ref "C9") (pin "2") (pinfunction "2_2") (pintype "passive"))
      (node (ref "GND_TP") (pin "X") (pinfunction "TESTP_X") (pintype "passive"))
      (node (ref "GND_TP1") (pin "X") (pinfunction "TESTP_X") (pintype "passive"))
      (node (ref "GROUND") (pin "1") (pinfunction "1_1") (pintype "passive"))
      (node (ref "ICSP") (pin "6") (pinfunction "6_6") (pintype "passive"))
      (node (ref "ICSP1") (pin "6") (pinfunction "6_6") (pintype "passive"))
      (node (ref "IOH") (pin "7") (pinfunction "7_7") (pintype "passive"))
      (node (ref "L") (pin "C") (pinfunction "C_C") (pintype "passive"))
      (node (ref "ON") (pin "C") (pinfunction "C_C") (pintype "passive"))
      (node (ref "PC1") (pin "-") (pinfunction "-_-") (pintype "passive"))
      (node (ref "PC2") (pin "-") (pinfunction "-_-") (pintype "passive"))
      (node (ref "POWER") (pin "6") (pinfunction "6_6") (pintype "passive"))
      (node (ref "POWER") (pin "7") (pinfunction "7_7") (pintype "passive"))
      (node (ref "RESET") (pin "1") (pinfunction "1_1") (pintype "passive"))
      (node (ref "RESET") (pin "2") (pinfunction "2_2") (pintype "passive"))
      (node (ref "RN1") (pin "7") (pinfunction "2_7") (pintype "passive"))
      (node (ref "RN2") (pin "5") (pinfunction "2_5") (pintype "passive"))
      (node (ref "U1") (pin "1") (pinfunction "GND/ADJ_1") (pintype "input"))
      (node (ref "U2") (pin "2") (pinfunction "GND_2") (pintype "power_in"))
      (node (ref "U3") (pin "3") (pinfunction "GND_3") (pintype "power_in"))
      (node (ref "U3") (pin "33") (pinfunction "PAD_33") (pintype "power_in"))
      (node (ref "U5") (pin "4") (pinfunction "V-_4") (pintype "power_in"))
      (node (ref "X1") (pin "1") (pinfunction "1_1") (pintype "power_in"))
      (node (ref "X1") (pin "3") (pinfunction "3_3") (pintype "power_in"))
      (node (ref "Y2") (pin "2") (pinfunction "2_2") (pintype "passive"))
      (node (ref "ZU4") (pin "22") (pinfunction "AGND_22") (pintype "power_in"))
      (node (ref "ZU4") (pin "8") (pinfunction "GND_8") (pintype "power_in"))
    )
    (net (code "59") (name "Net-(RN2B-2)") (class "Default")
      (node (ref "RN2") (pin "7") (pinfunction "2_7") (pintype "passive"))
      (node (ref "RX") (pin "A") (pinfunction "A_A") (pintype "passive"))
      (node (ref "TP_RXL") (pin "X") (pinfunction "TESTP_X") (pintype "passive"))
    )
    (net (code "60") (name "Net-(RN2C-2)") (class "Default")
      (node (ref "RN2") (pin "6") (pinfunction "2_6") (pintype "passive"))
      (node (ref "TP_TXL") (pin "X") (pinfunction "TESTP_X") (pintype "passive"))
      (node (ref "TX") (pin "A") (pinfunction "A_A") (pintype "passive"))
    )
    (net (code "61") (name "Net-(RN4C-2)") (class "Default")
      (node (ref "ON") (pin "A") (pinfunction "A_A") (pintype "passive"))
      (node (ref "RN4") (pin "5") (pinfunction "2_5") (pintype "passive"))
      (node (ref "RN4") (pin "6") (pinfunction "2_6") (pintype "passive"))
      (node (ref "TP_ONL") (pin "X") (pinfunction "TESTP_X") (pintype "passive"))
    )
    (net (code "62") (name "Net-(TP_LL-TESTP)") (class "Default")
      (node (ref "L") (pin "A") (pinfunction "A_A") (pintype "passive"))
      (node (ref "RN2") (pin "1") (pinfunction "1_1") (pintype "passive"))
      (node (ref "TP_LL") (pin "X") (pinfunction "TESTP_X") (pintype "passive"))
    )
    (net (code "63") (name "unconnected-(ORIGIN-TESTP-PadX)") (class "Default")
      (node (ref "ORIGIN") (pin "X") (pinfunction "TESTP_X") (pintype "passive"))
    )
    (net (code "64") (name "unconnected-(POWER-Pad1)") (class "Default")
      (node (ref "POWER") (pin "1") (pinfunction "1_1") (pintype "passive"))
    )
    (net (code "65") (name "unconnected-(RN3B-1-Pad2)") (class "Default")
      (node (ref "RN3") (pin "2") (pinfunction "1_2") (pintype "passive"))
    )
    (net (code "66") (name "unconnected-(RN3B-2-Pad7)") (class "Default")
      (node (ref "RN3") (pin "7") (pinfunction "2_7") (pintype "passive"))
    )
    (net (code "67") (name "unconnected-(RN3C-1-Pad3)") (class "Default")
      (node (ref "RN3") (pin "3") (pinfunction "1_3") (pintype "passive"))
    )
    (net (code "68") (name "unconnected-(RN3C-2-Pad6)") (class "Default")
      (node (ref "RN3") (pin "6") (pinfunction "2_6") (pintype "passive"))
    )
    (net (code "69") (name "unconnected-(U2-NC{slash}FB-Pad4)") (class "Default")
      (node (ref "U2") (pin "4") (pinfunction "NC/FB_4") (pintype "passive"))
    )
    (net (code "70") (name "unconnected-(U3-(AIN0{slash}INT1)PD1-Pad7)") (class "Default")
      (node (ref "U3") (pin "7") (pinfunction "(AIN0/INT1)PD1_7") (pintype "bidirectional"))
    )
    (net (code "71") (name "unconnected-(U3-(AIN2{slash}PCINT11)PC2-Pad5)") (class "Default")
      (node (ref "U3") (pin "5") (pinfunction "(AIN2/PCINT11)PC2_5") (pintype "bidirectional"))
    )
    (net (code "72") (name "unconnected-(U3-(INT4{slash}ICP1{slash}CLK0)PC7-Pad22)") (class "Default")
      (node (ref "U3") (pin "22") (pinfunction "(INT4/ICP1/CLK0)PC7_22") (pintype "bidirectional"))
    )
    (net (code "73") (name "unconnected-(U3-(OC0B{slash}INT0)PD0-Pad6)") (class "Default")
      (node (ref "U3") (pin "6") (pinfunction "(OC0B/INT0)PD0_6") (pintype "bidirectional"))
    )
    (net (code "74") (name "unconnected-(U3-(OC1A{slash}PCINT8)PC6-Pad23)") (class "Default")
      (node (ref "U3") (pin "23") (pinfunction "(OC1A/PCINT8)PC6_23") (pintype "bidirectional"))
    )
    (net (code "75") (name "unconnected-(U3-(PCINT9{slash}OC1B)PC5-Pad25)") (class "Default")
      (node (ref "U3") (pin "25") (pinfunction "(PCINT9/OC1B)PC5_25") (pintype "bidirectional"))
    )
    (net (code "76") (name "unconnected-(U3-(PCINT10)PC4-Pad26)") (class "Default")
      (node (ref "U3") (pin "26") (pinfunction "(PCINT10)PC4_26") (pintype "bidirectional"))
    )
    (net (code "77") (name "unconnected-(U3-(RTS{slash}AIN5{slash}INT6)PD6-Pad12)") (class "Default")
      (node (ref "U3") (pin "12") (pinfunction "(RTS/AIN5/INT6)PD6_12") (pintype "bidirectional"))
    )
    (net (code "78") (name "unconnected-(U3-(SS{slash}PCINT0)PB0-Pad14)") (class "Default")
      (node (ref "U3") (pin "14") (pinfunction "(SS/PCINT0)PB0_14") (pintype "bidirectional"))
    )
  )
)
